# Microcontroller.net
KiCad netlist of a schematic drawn in Altium Designer
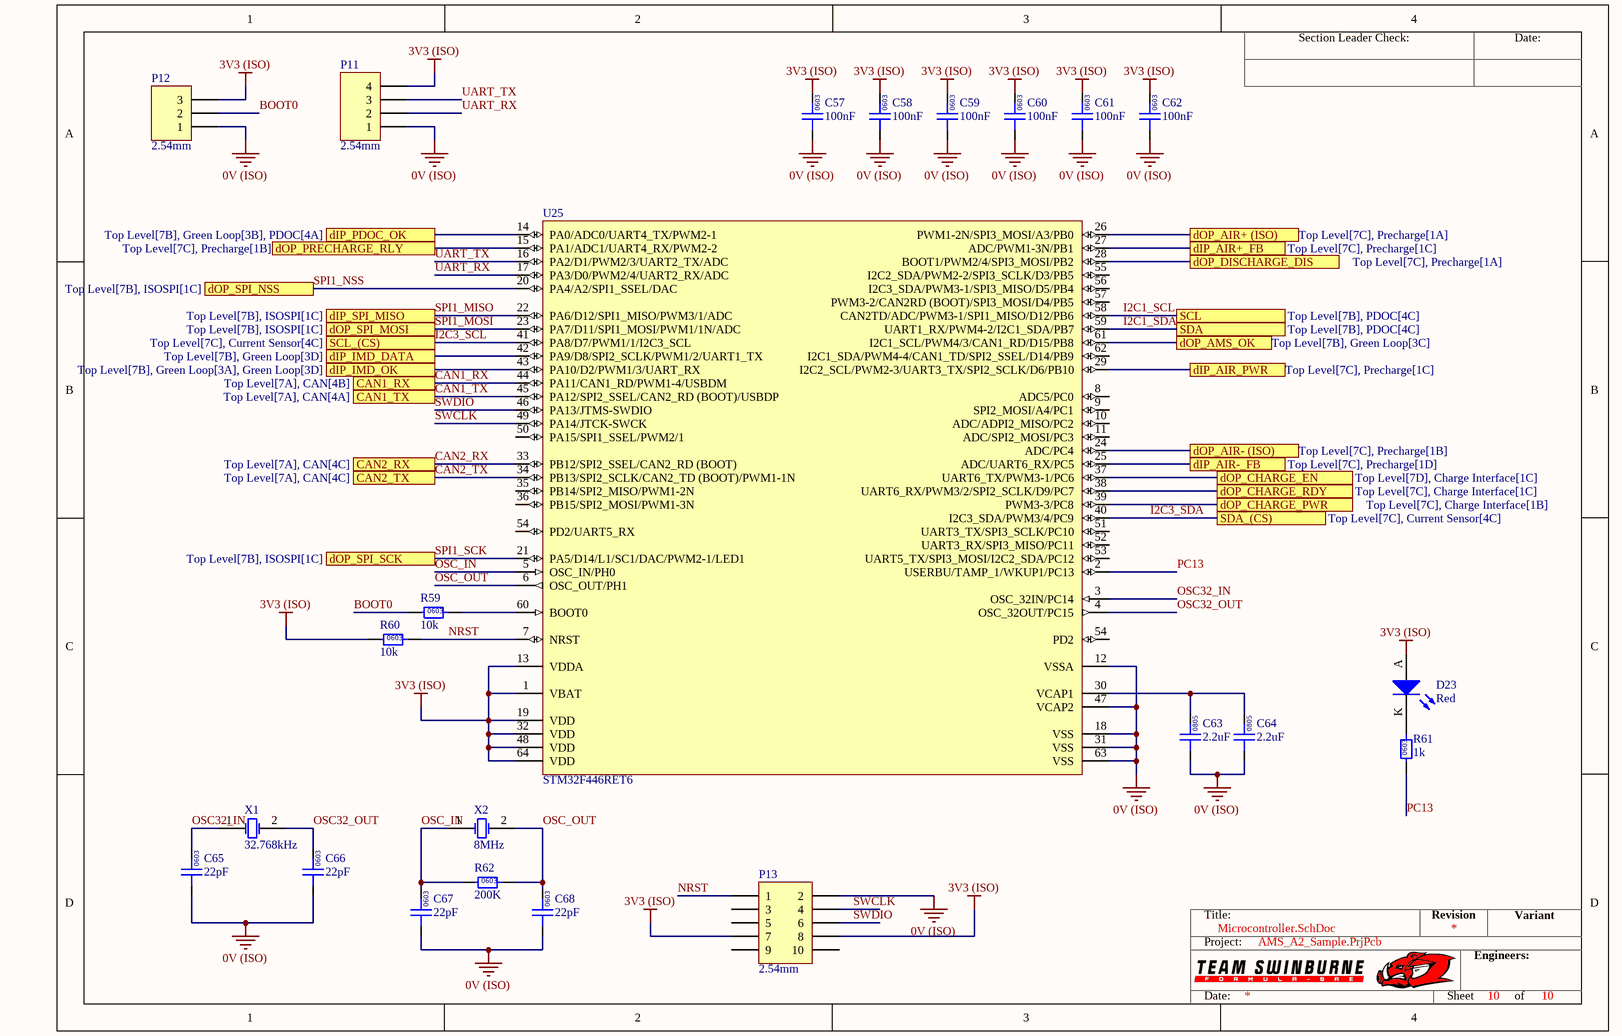
[diagram p0: Microcontroller.SchDoc]

(export (version "E")
  (design (tool "Eeschema 10.0.6"))
  (components
    (comp (ref "C57")
      (value "100nF")
      (footprint "0603")
      (fields
        (field (name "PART NUMBER") "GCM188L81H104KA57D")
        (field (name "MANUFACTURER") "muRata")
        (field (name "TOLERANCE") "±10%")
      )
      (libsource (lib "ts_standard_library") (part "Capacitor 0603"))
    )
    (comp (ref "C58")
      (value "100nF")
      (footprint "0603")
      (fields
        (field (name "PART NUMBER") "GCM188L81H104KA57D")
        (field (name "MANUFACTURER") "muRata")
        (field (name "TOLERANCE") "±10%")
      )
      (libsource (lib "ts_standard_library") (part "Capacitor 0603"))
    )
    (comp (ref "C59")
      (value "100nF")
      (footprint "0603")
      (fields
        (field (name "PART NUMBER") "GCM188L81H104KA57D")
        (field (name "MANUFACTURER") "muRata")
        (field (name "TOLERANCE") "±10%")
      )
      (libsource (lib "ts_standard_library") (part "Capacitor 0603"))
    )
    (comp (ref "C60")
      (value "100nF")
      (footprint "0603")
      (fields
        (field (name "PART NUMBER") "GCM188L81H104KA57D")
        (field (name "MANUFACTURER") "muRata")
        (field (name "TOLERANCE") "±10%")
      )
      (libsource (lib "ts_standard_library") (part "Capacitor 0603"))
    )
    (comp (ref "C61")
      (value "100nF")
      (footprint "0603")
      (fields
        (field (name "PART NUMBER") "GCM188L81H104KA57D")
        (field (name "MANUFACTURER") "muRata")
        (field (name "TOLERANCE") "±10%")
      )
      (libsource (lib "ts_standard_library") (part "Capacitor 0603"))
    )
    (comp (ref "C62")
      (value "100nF")
      (footprint "0603")
      (fields
        (field (name "PART NUMBER") "GCM188L81H104KA57D")
        (field (name "MANUFACTURER") "muRata")
        (field (name "TOLERANCE") "±10%")
      )
      (libsource (lib "ts_standard_library") (part "Capacitor 0603"))
    )
    (comp (ref "C63")
      (value "2.2uF")
      (footprint "0805")
      (fields
        (field (name "PART NUMBER") "GRM21BR71E225KE11L")
        (field (name "MANUFACTURER") "Murata Electronics")
        (field (name "TOLERANCE") "±10%")
      )
      (libsource (lib "ts_standard_library") (part "Capacitor 0805"))
    )
    (comp (ref "C64")
      (value "2.2uF")
      (footprint "0805")
      (fields
        (field (name "PART NUMBER") "GRM21BR71E225KE11L")
        (field (name "MANUFACTURER") "Murata Electronics")
        (field (name "TOLERANCE") "±10%")
      )
      (libsource (lib "ts_standard_library") (part "Capacitor 0805"))
    )
    (comp (ref "C65")
      (value "22pF")
      (footprint "0603")
      (fields
        (field (name "PART NUMBER") "GRM0335C1H220JA01D")
        (field (name "MANUFACTURER") "Murata Electronics")
        (field (name "TOLERANCE") "±5%")
      )
      (libsource (lib "ts_standard_library") (part "Capacitor 0603"))
    )
    (comp (ref "C66")
      (value "22pF")
      (footprint "0603")
      (fields
        (field (name "PART NUMBER") "GRM0335C1H220JA01D")
        (field (name "MANUFACTURER") "Murata Electronics")
        (field (name "TOLERANCE") "±5%")
      )
      (libsource (lib "ts_standard_library") (part "Capacitor 0603"))
    )
    (comp (ref "C67")
      (value "22pF")
      (footprint "0603")
      (fields
        (field (name "PART NUMBER") "GRM0335C1H220JA01D")
        (field (name "MANUFACTURER") "Murata Electronics")
        (field (name "TOLERANCE") "±5%")
      )
      (libsource (lib "ts_standard_library") (part "Capacitor 0603"))
    )
    (comp (ref "C68")
      (value "22pF")
      (footprint "0603")
      (fields
        (field (name "PART NUMBER") "GRM0335C1H220JA01D")
        (field (name "MANUFACTURER") "Murata Electronics")
        (field (name "TOLERANCE") "±5%")
      )
      (libsource (lib "ts_standard_library") (part "Capacitor 0603"))
    )
    (comp (ref "D23")
      (value "Red")
      (footprint "0805 LED")
      (description "Red LED Indication - Discrete 1.75V 0805 (2012 Metric)")
      (fields (field (name "PART NUMBER") "SML-210LTT86") (field (name "MANUFACTURER") "ROHM Semiconductor"))
      (libsource (lib "ts_20-standard-library") (part "LED"))
    )
    (comp (ref "P11")
      (value "2.54mm")
      (footprint "TH 2.54mm Header 1x4")
      (fields (field (name "PART NUMBER") "TH 2.54mm Header 1x4") (field (name "CONTACT") "NA"))
      (libsource (lib "ts_standard_connectors") (part "Header 1x4"))
    )
    (comp (ref "P12")
      (value "2.54mm")
      (footprint "TH 2.54mm Header 1x3")
      (fields (field (name "PART NUMBER") "TH 2.54mm Header 1x3") (field (name "CONTACT") "NA"))
      (libsource (lib "ts_standard_connectors") (part "Header 1x3"))
    )
    (comp (ref "P13")
      (value "2.54mm")
      (footprint "TH 2.54mm Header 2x5")
      (fields (field (name "PART NUMBER") "SMD 2.54mm Header 2x5") (field (name "CONTACT") "NA"))
      (libsource (lib "ts_standard_connectors") (part "Header 2x5"))
    )
    (comp (ref "R59")
      (value "10k")
      (footprint "0603")
      (fields
        (field (name "PART NUMBER") "RC0603FR-0710KL")
        (field (name "MANUFACTURER") "YAGEO")
        (field (name "TOLERANCE") "0.01")
      )
      (libsource (lib "ts_standard_library") (part "Resistor 0603"))
    )
    (comp (ref "R60")
      (value "10k")
      (footprint "0603")
      (fields
        (field (name "PART NUMBER") "RC0603FR-0710KL")
        (field (name "MANUFACTURER") "YAGEO")
        (field (name "TOLERANCE") "0.01")
      )
      (libsource (lib "ts_standard_library") (part "Resistor 0603"))
    )
    (comp (ref "R61")
      (value "1k")
      (footprint "0603")
      (fields
        (field (name "PART NUMBER") "RC0603FR-071KL")
        (field (name "MANUFACTURER") "YAGEO")
        (field (name "TOLERANCE") "0.01")
      )
      (libsource (lib "ts_standard_library") (part "Resistor 0603"))
    )
    (comp (ref "R62")
      (value "200K")
      (footprint "0603")
      (fields
        (field (name "PART NUMBER") "RC0603FR-0720KL")
        (field (name "MANUFACTURER") "YAGEO")
        (field (name "TOLERANCE") "0.01")
      )
      (libsource (lib "ts_standard_library") (part "Resistor 0603"))
    )
    (comp (ref "U25")
      (value "STM32F446RET6")
      (footprint "STM 64-LQFP")
      (description "ARM® Cortex®-M4 STM32F4 Microcontroller IC 32-Bit 180MHz 512KB (512K x 8) FLASH 64-LQFP (10x10)")
      (fields
        (field (name "MANUFACTURER") "STMicroelectronics")
        (field (name "DIGIKEY PART NUMBER") "497-15376-ND")
      )
      (libsource (lib "ts_20-standard-library") (part "STM32F446RET6"))
    )
    (comp (ref "X1")
      (value "32.768kHz")
      (footprint "EPSON 2-SMD")
      (fields
        (field (name "PART NUMBER") "FC-135 32.7680KA-A5")
        (field (name "MANUFACTURER") "EPSON")
        (field (name "DIGIKEY PART NUMBER") "SER4103TR-ND")
      )
      (libsource (lib "ts_standard_library") (part "Crystal"))
    )
    (comp (ref "X2")
      (value "8MHz")
      (footprint "ECS-80-18-30-JGN-TR")
      (fields
        (field (name "PART NUMBER") "ECS-80-18-30-JGN-TR")
        (field (name "MANUFACTURER") "ECS Inc")
        (field (name "DIGIKEY PART NUMBER") "XC2103CT-ND")
      )
      (libsource (lib "ts_standard_library") (part "Crystal"))
    )
  )
  (nets
    (net (code "1") (name "/BOOT0") (class "Default")
      (node (ref "P12") (pin "2") (pinfunction "2_2") (pintype "passive"))
      (node (ref "R59") (pin "1") (pinfunction "1_1") (pintype "passive"))
    )
    (net (code "2") (name "/CAN1_RX") (class "Default")
      (node (ref "U25") (pin "44") (pinfunction "PA11/CAN1_RD/PWM1-4/USBDM_44") (pintype "bidirectional"))
    )
    (net (code "3") (name "/CAN1_TX") (class "Default")
      (node (ref "U25") (pin "45") (pinfunction "PA12/SPI2_SSEL/CAN2_RD_(BOOT)/USBDP_45") (pintype "bidirectional"))
    )
    (net (code "4") (name "/CAN2_RX") (class "Default")
      (node (ref "U25") (pin "33") (pinfunction "PB12/SPI2_SSEL/CAN2_RD_(BOOT)_33") (pintype "bidirectional"))
    )
    (net (code "5") (name "/CAN2_TX") (class "Default")
      (node (ref "U25") (pin "34") (pinfunction "PB13/SPI2_SCLK/CAN2_TD_(BOOT)/PWM1-1N_34") (pintype "bidirectional"))
    )
    (net (code "6") (name "/I2C1_SCL") (class "Default")
      (node (ref "U25") (pin "58") (pinfunction "CAN2TD/ADC/PWM3-1/SPI1_MISO/D12/PB6_58") (pintype "bidirectional"))
    )
    (net (code "7") (name "/I2C1_SDA") (class "Default")
      (node (ref "U25") (pin "59") (pinfunction "UART1_RX/PWM4-2/I2C1_SDA/PB7_59") (pintype "bidirectional"))
    )
    (net (code "8") (name "/I2C3_SCL") (class "Default")
      (node (ref "U25") (pin "41") (pinfunction "PA8/D7/PWM1/1/I2C3_SCL_41") (pintype "bidirectional"))
    )
    (net (code "9") (name "/I2C3_SDA") (class "Default")
      (node (ref "U25") (pin "40") (pinfunction "I2C3_SDA/PWM3/4/PC9_40") (pintype "bidirectional"))
    )
    (net (code "10") (name "/NRST") (class "Default")
      (node (ref "P13") (pin "1") (pinfunction "1_1") (pintype "passive"))
      (node (ref "R60") (pin "2") (pinfunction "2_2") (pintype "passive"))
      (node (ref "U25") (pin "7") (pinfunction "NRST_7") (pintype "bidirectional"))
    )
    (net (code "11") (name "/OSC32_IN") (class "Default")
      (node (ref "C65") (pin "2") (pinfunction "2_2") (pintype "passive"))
      (node (ref "U25") (pin "3") (pinfunction "OSC_32IN/PC14_3") (pintype "input"))
      (node (ref "X1") (pin "1") (pinfunction "OSC1_1") (pintype "passive"))
    )
    (net (code "12") (name "/OSC32_OUT") (class "Default")
      (node (ref "C66") (pin "2") (pinfunction "2_2") (pintype "passive"))
      (node (ref "U25") (pin "4") (pinfunction "OSC_32OUT/PC15_4") (pintype "output"))
      (node (ref "X1") (pin "2") (pinfunction "OSC2_2") (pintype "passive"))
    )
    (net (code "13") (name "/OSC_IN") (class "Default")
      (node (ref "C67") (pin "2") (pinfunction "2_2") (pintype "passive"))
      (node (ref "R62") (pin "1") (pinfunction "1_1") (pintype "passive"))
      (node (ref "U25") (pin "5") (pinfunction "OSC_IN/PH0_5") (pintype "input"))
      (node (ref "X2") (pin "1") (pinfunction "OSC1_1") (pintype "passive"))
    )
    (net (code "14") (name "/OSC_OUT") (class "Default")
      (node (ref "C68") (pin "2") (pinfunction "2_2") (pintype "passive"))
      (node (ref "R62") (pin "2") (pinfunction "2_2") (pintype "passive"))
      (node (ref "U25") (pin "6") (pinfunction "OSC_OUT/PH1_6") (pintype "output"))
      (node (ref "X2") (pin "2") (pinfunction "OSC2_2") (pintype "passive"))
    )
    (net (code "15") (name "/PC13") (class "Default")
      (node (ref "R61") (pin "1") (pinfunction "1_1") (pintype "passive"))
      (node (ref "U25") (pin "2") (pinfunction "USERBU/TAMP_1/WKUP1/PC13_2") (pintype "bidirectional"))
    )
    (net (code "16") (name "/SPI1_MISO") (class "Default")
      (node (ref "U25") (pin "22") (pinfunction "PA6/D12/SPI1_MISO/PWM3/1/ADC_22") (pintype "bidirectional"))
    )
    (net (code "17") (name "/SPI1_MOSI") (class "Default")
      (node (ref "U25") (pin "23") (pinfunction "PA7/D11/SPI1_MOSI/PWM1/1N/ADC_23") (pintype "bidirectional"))
    )
    (net (code "18") (name "/SPI1_NSS") (class "Default")
      (node (ref "U25") (pin "20") (pinfunction "PA4/A2/SPI1_SSEL/DAC_20") (pintype "bidirectional"))
    )
    (net (code "19") (name "/SPI1_SCK") (class "Default")
      (node (ref "U25") (pin "21") (pinfunction "PA5/D14/L1/SC1/DAC/PWM2-1/LED1_21") (pintype "bidirectional"))
    )
    (net (code "20") (name "/SWCLK") (class "Default")
      (node (ref "P13") (pin "4") (pinfunction "4_4") (pintype "passive"))
      (node (ref "U25") (pin "49") (pinfunction "PA14/JTCK-SWCK_49") (pintype "bidirectional"))
    )
    (net (code "21") (name "/SWDIO") (class "Default")
      (node (ref "P13") (pin "6") (pinfunction "6_6") (pintype "passive"))
      (node (ref "U25") (pin "46") (pinfunction "PA13/JTMS-SWDIO_46") (pintype "bidirectional"))
    )
    (net (code "22") (name "/UART_RX") (class "Default")
      (node (ref "P11") (pin "2") (pinfunction "2_2") (pintype "passive"))
      (node (ref "U25") (pin "17") (pinfunction "PA3/D0/PWM2/4/UART2_RX/ADC_17") (pintype "bidirectional"))
    )
    (net (code "23") (name "/UART_TX") (class "Default")
      (node (ref "P11") (pin "3") (pinfunction "3_3") (pintype "passive"))
      (node (ref "U25") (pin "16") (pinfunction "PA2/D1/PWM2/3/UART2_TX/ADC_16") (pintype "bidirectional"))
    )
    (net (code "24") (name "/dIP_AIR+_FB") (class "Default")
      (node (ref "U25") (pin "27") (pinfunction "ADC/PWM1-3N/PB1_27") (pintype "bidirectional"))
    )
    (net (code "25") (name "/dIP_AIR-_FB") (class "Default")
      (node (ref "U25") (pin "25") (pinfunction "ADC/UART6_RX/PC5_25") (pintype "bidirectional"))
    )
    (net (code "26") (name "/dIP_AIR_PWR") (class "Default")
      (node (ref "U25") (pin "29") (pinfunction "I2C2_SCL/PWM2-3/UART3_TX/SPI2_SCLK/D6/PB10_29") (pintype "bidirectional"))
    )
    (net (code "27") (name "/dIP_IMD_DATA") (class "Default")
      (node (ref "U25") (pin "42") (pinfunction "PA9/D8/SPI2_SCLK/PWM1/2/UART1_TX_42") (pintype "bidirectional"))
    )
    (net (code "28") (name "/dIP_IMD_OK") (class "Default")
      (node (ref "U25") (pin "43") (pinfunction "PA10/D2/PWM1/3/UART_RX_43") (pintype "bidirectional"))
    )
    (net (code "29") (name "/dIP_PDOC_OK") (class "Default")
      (node (ref "U25") (pin "14") (pinfunction "PA0/ADC0/UART4_TX/PWM2-1_14") (pintype "bidirectional"))
    )
    (net (code "30") (name "/dOP_AIR+ (ISO)") (class "Default")
      (node (ref "U25") (pin "26") (pinfunction "PWM1-2N/SPI3_MOSI/A3/PB0_26") (pintype "bidirectional"))
    )
    (net (code "31") (name "/dOP_AIR- (ISO)") (class "Default")
      (node (ref "U25") (pin "24") (pinfunction "ADC/PC4_24") (pintype "bidirectional"))
    )
    (net (code "32") (name "/dOP_AMS_OK") (class "Default")
      (node (ref "U25") (pin "61") (pinfunction "I2C1_SCL/PWM4/3/CAN1_RD/D15/PB8_61") (pintype "bidirectional"))
    )
    (net (code "33") (name "/dOP_CHARGE_EN") (class "Default")
      (node (ref "U25") (pin "37") (pinfunction "UART6_TX/PWM3-1/PC6_37") (pintype "bidirectional"))
    )
    (net (code "34") (name "/dOP_CHARGE_PWR") (class "Default")
      (node (ref "U25") (pin "39") (pinfunction "PWM3-3/PC8_39") (pintype "bidirectional"))
    )
    (net (code "35") (name "/dOP_CHARGE_RDY") (class "Default")
      (node (ref "U25") (pin "38") (pinfunction "UART6_RX/PWM3/2/SPI2_SCLK/D9/PC7_38") (pintype "bidirectional"))
    )
    (net (code "36") (name "/dOP_DISCHARGE_DIS") (class "Default")
      (node (ref "U25") (pin "28") (pinfunction "BOOT1/PWM2/4/SPI3_MOSI/PB2_28") (pintype "bidirectional"))
    )
    (net (code "37") (name "/dOP_PRECHARGE_RLY") (class "Default")
      (node (ref "U25") (pin "15") (pinfunction "PA1/ADC1/UART4_RX/PWM2-2_15") (pintype "bidirectional"))
    )
    (net (code "38") (name "0V (ISO)") (class "Default")
      (node (ref "C57") (pin "1") (pinfunction "1_1") (pintype "passive"))
      (node (ref "C58") (pin "1") (pinfunction "1_1") (pintype "passive"))
      (node (ref "C59") (pin "1") (pinfunction "1_1") (pintype "passive"))
      (node (ref "C60") (pin "1") (pinfunction "1_1") (pintype "passive"))
      (node (ref "C61") (pin "1") (pinfunction "1_1") (pintype "passive"))
      (node (ref "C62") (pin "1") (pinfunction "1_1") (pintype "passive"))
      (node (ref "C63") (pin "1") (pinfunction "1_1") (pintype "passive"))
      (node (ref "C64") (pin "1") (pinfunction "1_1") (pintype "passive"))
      (node (ref "C65") (pin "1") (pinfunction "1_1") (pintype "passive"))
      (node (ref "C66") (pin "1") (pinfunction "1_1") (pintype "passive"))
      (node (ref "C67") (pin "1") (pinfunction "1_1") (pintype "passive"))
      (node (ref "C68") (pin "1") (pinfunction "1_1") (pintype "passive"))
      (node (ref "P11") (pin "1") (pinfunction "1_1") (pintype "passive"))
      (node (ref "P12") (pin "1") (pinfunction "1_1") (pintype "passive"))
      (node (ref "P13") (pin "2") (pinfunction "2_2") (pintype "passive"))
      (node (ref "U25") (pin "12") (pinfunction "VSSA_12") (pintype "power_in"))
      (node (ref "U25") (pin "18") (pinfunction "VSS_18") (pintype "power_in"))
      (node (ref "U25") (pin "31") (pinfunction "VSS_31") (pintype "power_in"))
      (node (ref "U25") (pin "47") (pinfunction "VCAP2_47") (pintype "power_in"))
      (node (ref "U25") (pin "63") (pinfunction "VSS_63") (pintype "power_in"))
    )
    (net (code "39") (name "3V3 (ISO)") (class "Default")
      (node (ref "C57") (pin "2") (pinfunction "2_2") (pintype "passive"))
      (node (ref "C58") (pin "2") (pinfunction "2_2") (pintype "passive"))
      (node (ref "C59") (pin "2") (pinfunction "2_2") (pintype "passive"))
      (node (ref "C60") (pin "2") (pinfunction "2_2") (pintype "passive"))
      (node (ref "C61") (pin "2") (pinfunction "2_2") (pintype "passive"))
      (node (ref "C62") (pin "2") (pinfunction "2_2") (pintype "passive"))
      (node (ref "D23") (pin "A") (pinfunction "A_A") (pintype "passive"))
      (node (ref "P11") (pin "4") (pinfunction "4_4") (pintype "passive"))
      (node (ref "P12") (pin "3") (pinfunction "3_3") (pintype "passive"))
      (node (ref "P13") (pin "7") (pinfunction "7_7") (pintype "passive"))
      (node (ref "P13") (pin "8") (pinfunction "8_8") (pintype "passive"))
      (node (ref "R60") (pin "1") (pinfunction "1_1") (pintype "passive"))
      (node (ref "U25") (pin "1") (pinfunction "VBAT_1") (pintype "power_in"))
      (node (ref "U25") (pin "13") (pinfunction "VDDA_13") (pintype "power_in"))
      (node (ref "U25") (pin "19") (pinfunction "VDD_19") (pintype "power_in"))
      (node (ref "U25") (pin "32") (pinfunction "VDD_32") (pintype "power_in"))
      (node (ref "U25") (pin "48") (pinfunction "VDD_48") (pintype "power_in"))
      (node (ref "U25") (pin "64") (pinfunction "VDD_64") (pintype "power_in"))
    )
    (net (code "40") (name "Net-(D23-PadK)") (class "Default")
      (node (ref "D23") (pin "K") (pinfunction "K_K") (pintype "passive"))
      (node (ref "R61") (pin "2") (pinfunction "2_2") (pintype "passive"))
    )
    (net (code "41") (name "Net-(U25-BOOT0)") (class "Default")
      (node (ref "R59") (pin "2") (pinfunction "2_2") (pintype "passive"))
      (node (ref "U25") (pin "60") (pinfunction "BOOT0_60") (pintype "input"))
    )
    (net (code "42") (name "Net-(U25-VCAP1)") (class "Default")
      (node (ref "C63") (pin "2") (pinfunction "2_2") (pintype "passive"))
      (node (ref "C64") (pin "2") (pinfunction "2_2") (pintype "passive"))
      (node (ref "U25") (pin "30") (pinfunction "VCAP1_30") (pintype "power_in"))
    )
    (net (code "43") (name "unconnected-(P13-Pad3)") (class "Default")
      (node (ref "P13") (pin "3") (pinfunction "3_3") (pintype "passive"))
    )
    (net (code "44") (name "unconnected-(P13-Pad5)") (class "Default")
      (node (ref "P13") (pin "5") (pinfunction "5_5") (pintype "passive"))
    )
    (net (code "45") (name "unconnected-(P13-Pad9)") (class "Default")
      (node (ref "P13") (pin "9") (pinfunction "9_9") (pintype "passive"))
    )
    (net (code "46") (name "unconnected-(P13-Pad10)") (class "Default")
      (node (ref "P13") (pin "10") (pinfunction "10_10") (pintype "passive"))
    )
    (net (code "47") (name "unconnected-(U25-ADC5{slash}PC0-Pad8)") (class "Default")
      (node (ref "U25") (pin "8") (pinfunction "ADC5/PC0_8") (pintype "bidirectional"))
    )
    (net (code "48") (name "unconnected-(U25-ADC{slash}ADPI2_MISO{slash}PC2-Pad10)") (class "Default")
      (node (ref "U25") (pin "10") (pinfunction "ADC/ADPI2_MISO/PC2_10") (pintype "bidirectional"))
    )
    (net (code "49") (name "unconnected-(U25-ADC{slash}SPI2_MOSI{slash}PC3-Pad11)") (class "Default")
      (node (ref "U25") (pin "11") (pinfunction "ADC/SPI2_MOSI/PC3_11") (pintype "bidirectional"))
    )
    (net (code "50") (name "unconnected-(U25-I2C1_SDA{slash}PWM4-4{slash}CAN1_TD{slash}SPI2_SSEL{slash}D14{slash}PB9-Pad62)") (class "Default")
      (node (ref "U25") (pin "62") (pinfunction "I2C1_SDA/PWM4-4/CAN1_TD/SPI2_SSEL/D14/PB9_62") (pintype "bidirectional"))
    )
    (net (code "51") (name "unconnected-(U25-I2C2_SDA{slash}PWM2-2{slash}SPI3_SCLK{slash}D3{slash}PB5-Pad55)") (class "Default")
      (node (ref "U25") (pin "55") (pinfunction "I2C2_SDA/PWM2-2/SPI3_SCLK/D3/PB5_55") (pintype "bidirectional"))
    )
    (net (code "52") (name "unconnected-(U25-I2C3_SDA{slash}PWM3-1{slash}SPI3_MISO{slash}D5{slash}PB4-Pad56)") (class "Default")
      (node (ref "U25") (pin "56") (pinfunction "I2C3_SDA/PWM3-1/SPI3_MISO/D5/PB4_56") (pintype "bidirectional"))
    )
    (net (code "53") (name "unconnected-(U25-PA15{slash}SPI1_SSEL{slash}PWM2{slash}1-Pad50)") (class "Default")
      (node (ref "U25") (pin "50") (pinfunction "PA15/SPI1_SSEL/PWM2/1_50") (pintype "bidirectional"))
    )
    (net (code "54") (name "unconnected-(U25-PB14{slash}SPI2_MISO{slash}PWM1-2N-Pad35)") (class "Default")
      (node (ref "U25") (pin "35") (pinfunction "PB14/SPI2_MISO/PWM1-2N_35") (pintype "bidirectional"))
    )
    (net (code "55") (name "unconnected-(U25-PB15{slash}SPI2_MOSI{slash}PWM1-3N-Pad36)") (class "Default")
      (node (ref "U25") (pin "36") (pinfunction "PB15/SPI2_MOSI/PWM1-3N_36") (pintype "bidirectional"))
    )
    (net (code "56") (name "unconnected-(U25-PD2-Pad54)") (class "Default")
      (node (ref "U25") (pin "54") (pinfunction "PD2_54") (pintype "bidirectional"))
    )
    (net (code "57") (name "unconnected-(U25-PD2{slash}UART5_RX-Pad54)") (class "Default")
      (node (ref "U25") (pin "54") (pinfunction "PD2/UART5_RX_54") (pintype "bidirectional"))
    )
    (net (code "58") (name "unconnected-(U25-PWM3-2{slash}CAN2RD_(BOOT){slash}SPI3_MOSI{slash}D4{slash}PB5-Pad57)") (class "Default")
      (node (ref "U25") (pin "57") (pinfunction "PWM3-2/CAN2RD_(BOOT)/SPI3_MOSI/D4/PB5_57") (pintype "bidirectional"))
    )
    (net (code "59") (name "unconnected-(U25-SPI2_MOSI{slash}A4{slash}PC1-Pad9)") (class "Default")
      (node (ref "U25") (pin "9") (pinfunction "SPI2_MOSI/A4/PC1_9") (pintype "bidirectional"))
    )
    (net (code "60") (name "unconnected-(U25-UART3_RX{slash}SPI3_MISO{slash}PC11-Pad52)") (class "Default")
      (node (ref "U25") (pin "52") (pinfunction "UART3_RX/SPI3_MISO/PC11_52") (pintype "bidirectional"))
    )
    (net (code "61") (name "unconnected-(U25-UART3_TX{slash}SPI3_SCLK{slash}PC10-Pad51)") (class "Default")
      (node (ref "U25") (pin "51") (pinfunction "UART3_TX/SPI3_SCLK/PC10_51") (pintype "bidirectional"))
    )
    (net (code "62") (name "unconnected-(U25-UART5_TX{slash}SPI3_MOSI{slash}I2C2_SDA{slash}PC12-Pad53)") (class "Default")
      (node (ref "U25") (pin "53") (pinfunction "UART5_TX/SPI3_MOSI/I2C2_SDA/PC12_53") (pintype "bidirectional"))
    )
  )
)
